# untitled.net
KiCad netlist of a schematic drawn in EAGLE
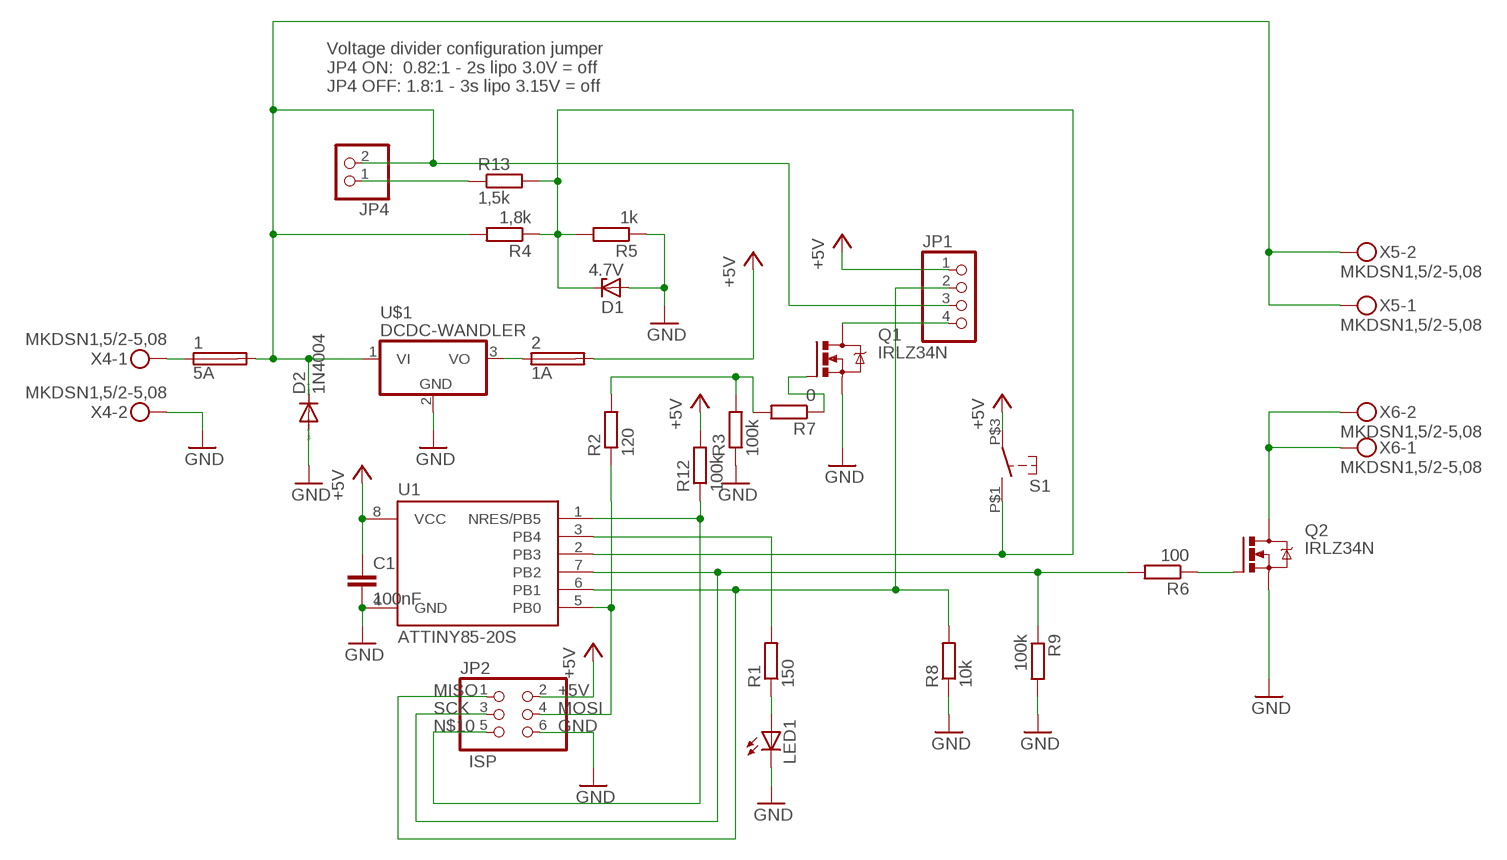
[diagram p0: schematic, sheet 1]

(export (version "E")
  (design (tool "Eeschema 10.0.6"))
  (components
    (comp (ref "1")
      (value "5A")
      (footprint "eagle-import:SH22,5A")
      (libsource (lib "eagle-import") (part "FUSESH22,5A"))
    )
    (comp (ref "2")
      (value "1A")
      (footprint "eagle-import:SH22,5A")
      (libsource (lib "eagle-import") (part "FUSESH22,5A"))
    )
    (comp (ref "C1")
      (value "100nF")
      (footprint "eagle-import:C0805")
      (libsource (lib "eagle-import") (part "C-EUC0805"))
    )
    (comp (ref "D1")
      (value "4.7V")
      (footprint "eagle-import:SOT23")
      (libsource (lib "eagle-import") (part "ZENER-DIODESOT23"))
    )
    (comp (ref "D2")
      (value "1N4004")
      (footprint "eagle-import:DO41-10")
      (libsource (lib "eagle-import") (part "1N4004"))
    )
    (comp (ref "JP1")
      (value "PINHD-1X4")
      (footprint "eagle-import:1X04")
      (libsource (lib "eagle-import") (part "PINHD-1X4"))
    )
    (comp (ref "JP2")
      (value "PINHD-2X3")
      (footprint "eagle-import:2X03")
      (libsource (lib "eagle-import") (part "PINHD-2X3"))
    )
    (comp (ref "JP4")
      (value "PINHD-1X2")
      (footprint "eagle-import:1X02")
      (libsource (lib "eagle-import") (part "PINHD-1X2"))
    )
    (comp (ref "LED1")
      (value "LED3MM")
      (footprint "eagle-import:LED3MM")
      (libsource (lib "eagle-import") (part "LED3MM"))
    )
    (comp (ref "Q1")
      (value "IRLZ34N")
      (footprint "eagle-import:TO220BH")
      (libsource (lib "eagle-import") (part "IRLZ44Z"))
    )
    (comp (ref "Q2")
      (value "IRLZ34N")
      (footprint "eagle-import:TO220BH")
      (libsource (lib "eagle-import") (part "IRLZ44Z"))
    )
    (comp (ref "R1")
      (value "150")
      (footprint "eagle-import:R1206")
      (libsource (lib "eagle-import") (part "R-EU_R1206"))
    )
    (comp (ref "R2")
      (value "120")
      (footprint "eagle-import:R1206")
      (libsource (lib "eagle-import") (part "R-EU_R1206"))
    )
    (comp (ref "R3")
      (value "100k")
      (footprint "eagle-import:R1206")
      (libsource (lib "eagle-import") (part "R-EU_R1206"))
    )
    (comp (ref "R4")
      (value "1,8k")
      (footprint "eagle-import:R1206")
      (libsource (lib "eagle-import") (part "R-EU_R1206"))
    )
    (comp (ref "R5")
      (value "1k")
      (footprint "eagle-import:R1206")
      (libsource (lib "eagle-import") (part "R-EU_R1206"))
    )
    (comp (ref "R6")
      (value "100")
      (footprint "eagle-import:R1206")
      (libsource (lib "eagle-import") (part "R-EU_R1206"))
    )
    (comp (ref "R7")
      (value "0")
      (footprint "eagle-import:R1206")
      (libsource (lib "eagle-import") (part "R-EU_R1206"))
    )
    (comp (ref "R8")
      (value "10k")
      (footprint "eagle-import:R1206")
      (libsource (lib "eagle-import") (part "R-EU_R1206"))
    )
    (comp (ref "R9")
      (value "100k")
      (footprint "eagle-import:R1206")
      (libsource (lib "eagle-import") (part "R-EU_R1206"))
    )
    (comp (ref "R12")
      (value "100k")
      (footprint "eagle-import:R1206")
      (libsource (lib "eagle-import") (part "R-EU_R1206"))
    )
    (comp (ref "R13")
      (value "1,5k")
      (footprint "eagle-import:R1206")
      (libsource (lib "eagle-import") (part "R-EU_R1206"))
    )
    (comp (ref "S1")
      (value "SCHLIESSER_TASTSCHALTER")
      (footprint "eagle-import:NAMAE-JTP-1130")
      (libsource (lib "eagle-import") (part "SCHLIESSER_TASTSCHALTER"))
    )
    (comp (ref "U$1")
      (value "DCDC-WANDLER")
      (footprint "eagle-import:TRACOPOWER-DCDCWANDER-TSR1")
      (libsource (lib "eagle-import") (part "DCDC-WANDLER"))
    )
    (comp (ref "U1")
      (value "ATTINY85-20S")
      (footprint "eagle-import:SOIC8_EIAJ_208MIL")
      (libsource (lib "eagle-import") (part "ATTINY85S-20"))
    )
    (comp (ref "X4")
      (value "MKDSN1,5/2-5,08")
      (footprint "eagle-import:MKDSN1,5_2-5,08")
      (libsource (lib "eagle-import") (part "MKDSN1,5/2-5,08"))
    )
    (comp (ref "X5")
      (value "MKDSN1,5/2-5,08")
      (footprint "eagle-import:MKDSN1,5_2-5,08")
      (libsource (lib "eagle-import") (part "MKDSN1,5/2-5,08"))
    )
    (comp (ref "X6")
      (value "MKDSN1,5/2-5,08")
      (footprint "eagle-import:MKDSN1,5_2-5,08")
      (libsource (lib "eagle-import") (part "MKDSN1,5/2-5,08"))
    )
  )
  (nets
    (net (code "1") (name "+5V") (class "Default")
      (node (ref "2") (pin "2") (pinfunction "2_2") (pintype "passive"))
      (node (ref "C1") (pin "1") (pinfunction "1_1") (pintype "passive"))
      (node (ref "JP1") (pin "1") (pinfunction "1_1") (pintype "passive"))
      (node (ref "JP2") (pin "2") (pinfunction "2_2") (pintype "passive"))
      (node (ref "R12") (pin "2") (pinfunction "2_2") (pintype "passive"))
      (node (ref "S1") (pin "P$3") (pinfunction "4_P$3") (pintype "input"))
      (node (ref "U1") (pin "8") (pinfunction "VCC_8") (pintype "power_in"))
    )
    (net (code "2") (name "/MISO") (class "Default")
      (node (ref "JP1") (pin "2") (pinfunction "2_2") (pintype "passive"))
      (node (ref "JP2") (pin "1") (pinfunction "1_1") (pintype "passive"))
      (node (ref "R8") (pin "2") (pinfunction "2_2") (pintype "passive"))
      (node (ref "U1") (pin "6") (pinfunction "PB1_6") (pintype "bidirectional"))
    )
    (net (code "3") (name "/MOSI") (class "Default")
      (node (ref "JP2") (pin "4") (pinfunction "4_4") (pintype "passive"))
      (node (ref "R2") (pin "1") (pinfunction "1_1") (pintype "passive"))
      (node (ref "U1") (pin "5") (pinfunction "PB0_5") (pintype "bidirectional"))
    )
    (net (code "4") (name "/N$10") (class "Default")
      (node (ref "JP2") (pin "5") (pinfunction "5_5") (pintype "passive"))
      (node (ref "R12") (pin "1") (pinfunction "1_1") (pintype "passive"))
      (node (ref "U1") (pin "1") (pinfunction "NRES/PB5_1") (pintype "bidirectional"))
    )
    (net (code "5") (name "/SCK") (class "Default")
      (node (ref "JP2") (pin "3") (pinfunction "3_3") (pintype "passive"))
      (node (ref "R6") (pin "2") (pinfunction "2_2") (pintype "passive"))
      (node (ref "R9") (pin "1") (pinfunction "1_1") (pintype "passive"))
      (node (ref "U1") (pin "7") (pinfunction "PB2_7") (pintype "bidirectional"))
    )
    (net (code "6") (name "GND") (class "Default")
      (node (ref "C1") (pin "2") (pinfunction "2_2") (pintype "passive"))
      (node (ref "D1") (pin "1") (pinfunction "A_1") (pintype "passive"))
      (node (ref "D2") (pin "A") (pinfunction "A_A") (pintype "passive"))
      (node (ref "JP2") (pin "6") (pinfunction "6_6") (pintype "passive"))
      (node (ref "LED1") (pin "K") (pinfunction "C_K") (pintype "passive"))
      (node (ref "Q1") (pin "S") (pinfunction "S_S") (pintype "passive"))
      (node (ref "Q2") (pin "S") (pinfunction "S_S") (pintype "passive"))
      (node (ref "R3") (pin "1") (pinfunction "1_1") (pintype "passive"))
      (node (ref "R5") (pin "1") (pinfunction "1_1") (pintype "passive"))
      (node (ref "R8") (pin "1") (pinfunction "1_1") (pintype "passive"))
      (node (ref "R9") (pin "2") (pinfunction "2_2") (pintype "passive"))
      (node (ref "U$1") (pin "2") (pinfunction "GND_2") (pintype "passive"))
      (node (ref "U1") (pin "4") (pinfunction "GND_4") (pintype "power_in"))
      (node (ref "X4") (pin "2") (pinfunction "KL_2") (pintype "passive"))
    )
    (net (code "7") (name "Net-(D1-C)") (class "Default")
      (node (ref "D1") (pin "3") (pinfunction "C_3") (pintype "passive"))
      (node (ref "R13") (pin "2") (pinfunction "2_2") (pintype "passive"))
      (node (ref "R4") (pin "1") (pinfunction "1_1") (pintype "passive"))
      (node (ref "R5") (pin "2") (pinfunction "2_2") (pintype "passive"))
      (node (ref "S1") (pin "P$1") (pinfunction "3_P$1") (pintype "input"))
      (node (ref "U1") (pin "2") (pinfunction "PB3_2") (pintype "bidirectional"))
    )
    (net (code "8") (name "Net-(JP1-Pad4)") (class "Default")
      (node (ref "JP1") (pin "4") (pinfunction "4_4") (pintype "passive"))
      (node (ref "Q1") (pin "D") (pinfunction "D_D") (pintype "passive"))
    )
    (net (code "9") (name "Net-(JP4-Pad1)") (class "Default")
      (node (ref "JP4") (pin "1") (pinfunction "1_1") (pintype "passive"))
      (node (ref "R13") (pin "1") (pinfunction "1_1") (pintype "passive"))
    )
    (net (code "10") (name "Net-(LED1-PadA)") (class "Default")
      (node (ref "LED1") (pin "A") (pinfunction "A_A") (pintype "passive"))
      (node (ref "R1") (pin "1") (pinfunction "1_1") (pintype "passive"))
    )
    (net (code "11") (name "Net-(Q1-PadG)") (class "Default")
      (node (ref "Q1") (pin "G") (pinfunction "G_G") (pintype "passive"))
      (node (ref "R7") (pin "1") (pinfunction "1_1") (pintype "passive"))
    )
    (net (code "12") (name "Net-(Q2-PadG)") (class "Default")
      (node (ref "Q2") (pin "G") (pinfunction "G_G") (pintype "passive"))
      (node (ref "R6") (pin "1") (pinfunction "1_1") (pintype "passive"))
    )
    (net (code "13") (name "Net-(R2-Pad2)") (class "Default")
      (node (ref "R2") (pin "2") (pinfunction "2_2") (pintype "passive"))
      (node (ref "R3") (pin "2") (pinfunction "2_2") (pintype "passive"))
      (node (ref "R7") (pin "2") (pinfunction "2_2") (pintype "passive"))
    )
    (net (code "14") (name "Net-(U$1-VI)") (class "Default")
      (node (ref "1") (pin "2") (pinfunction "2_2") (pintype "passive"))
      (node (ref "D2") (pin "C") (pinfunction "C_C") (pintype "passive"))
      (node (ref "JP1") (pin "3") (pinfunction "3_3") (pintype "passive"))
      (node (ref "JP4") (pin "2") (pinfunction "2_2") (pintype "passive"))
      (node (ref "R4") (pin "2") (pinfunction "2_2") (pintype "passive"))
      (node (ref "U$1") (pin "1") (pinfunction "VI_1") (pintype "input"))
      (node (ref "X5") (pin "1") (pinfunction "KL_1") (pintype "passive"))
      (node (ref "X5") (pin "2") (pinfunction "KL_2") (pintype "passive"))
    )
    (net (code "15") (name "Net-(U$1-VO)") (class "Default")
      (node (ref "2") (pin "1") (pinfunction "1_1") (pintype "passive"))
      (node (ref "U$1") (pin "3") (pinfunction "VO_3") (pintype "passive"))
    )
    (net (code "16") (name "Net-(U1-PB4)") (class "Default")
      (node (ref "R1") (pin "2") (pinfunction "2_2") (pintype "passive"))
      (node (ref "U1") (pin "3") (pinfunction "PB4_3") (pintype "bidirectional"))
    )
    (net (code "17") (name "Net-(X4A-KL)") (class "Default")
      (node (ref "1") (pin "1") (pinfunction "1_1") (pintype "passive"))
      (node (ref "X4") (pin "1") (pinfunction "KL_1") (pintype "passive"))
    )
    (net (code "18") (name "Net-(X6A-KL)") (class "Default")
      (node (ref "Q2") (pin "D") (pinfunction "D_D") (pintype "passive"))
      (node (ref "X6") (pin "1") (pinfunction "KL_1") (pintype "passive"))
      (node (ref "X6") (pin "2") (pinfunction "KL_2") (pintype "passive"))
    )
  )
)
